# main_top.net
KiCad netlist of a schematic drawn in EAGLE
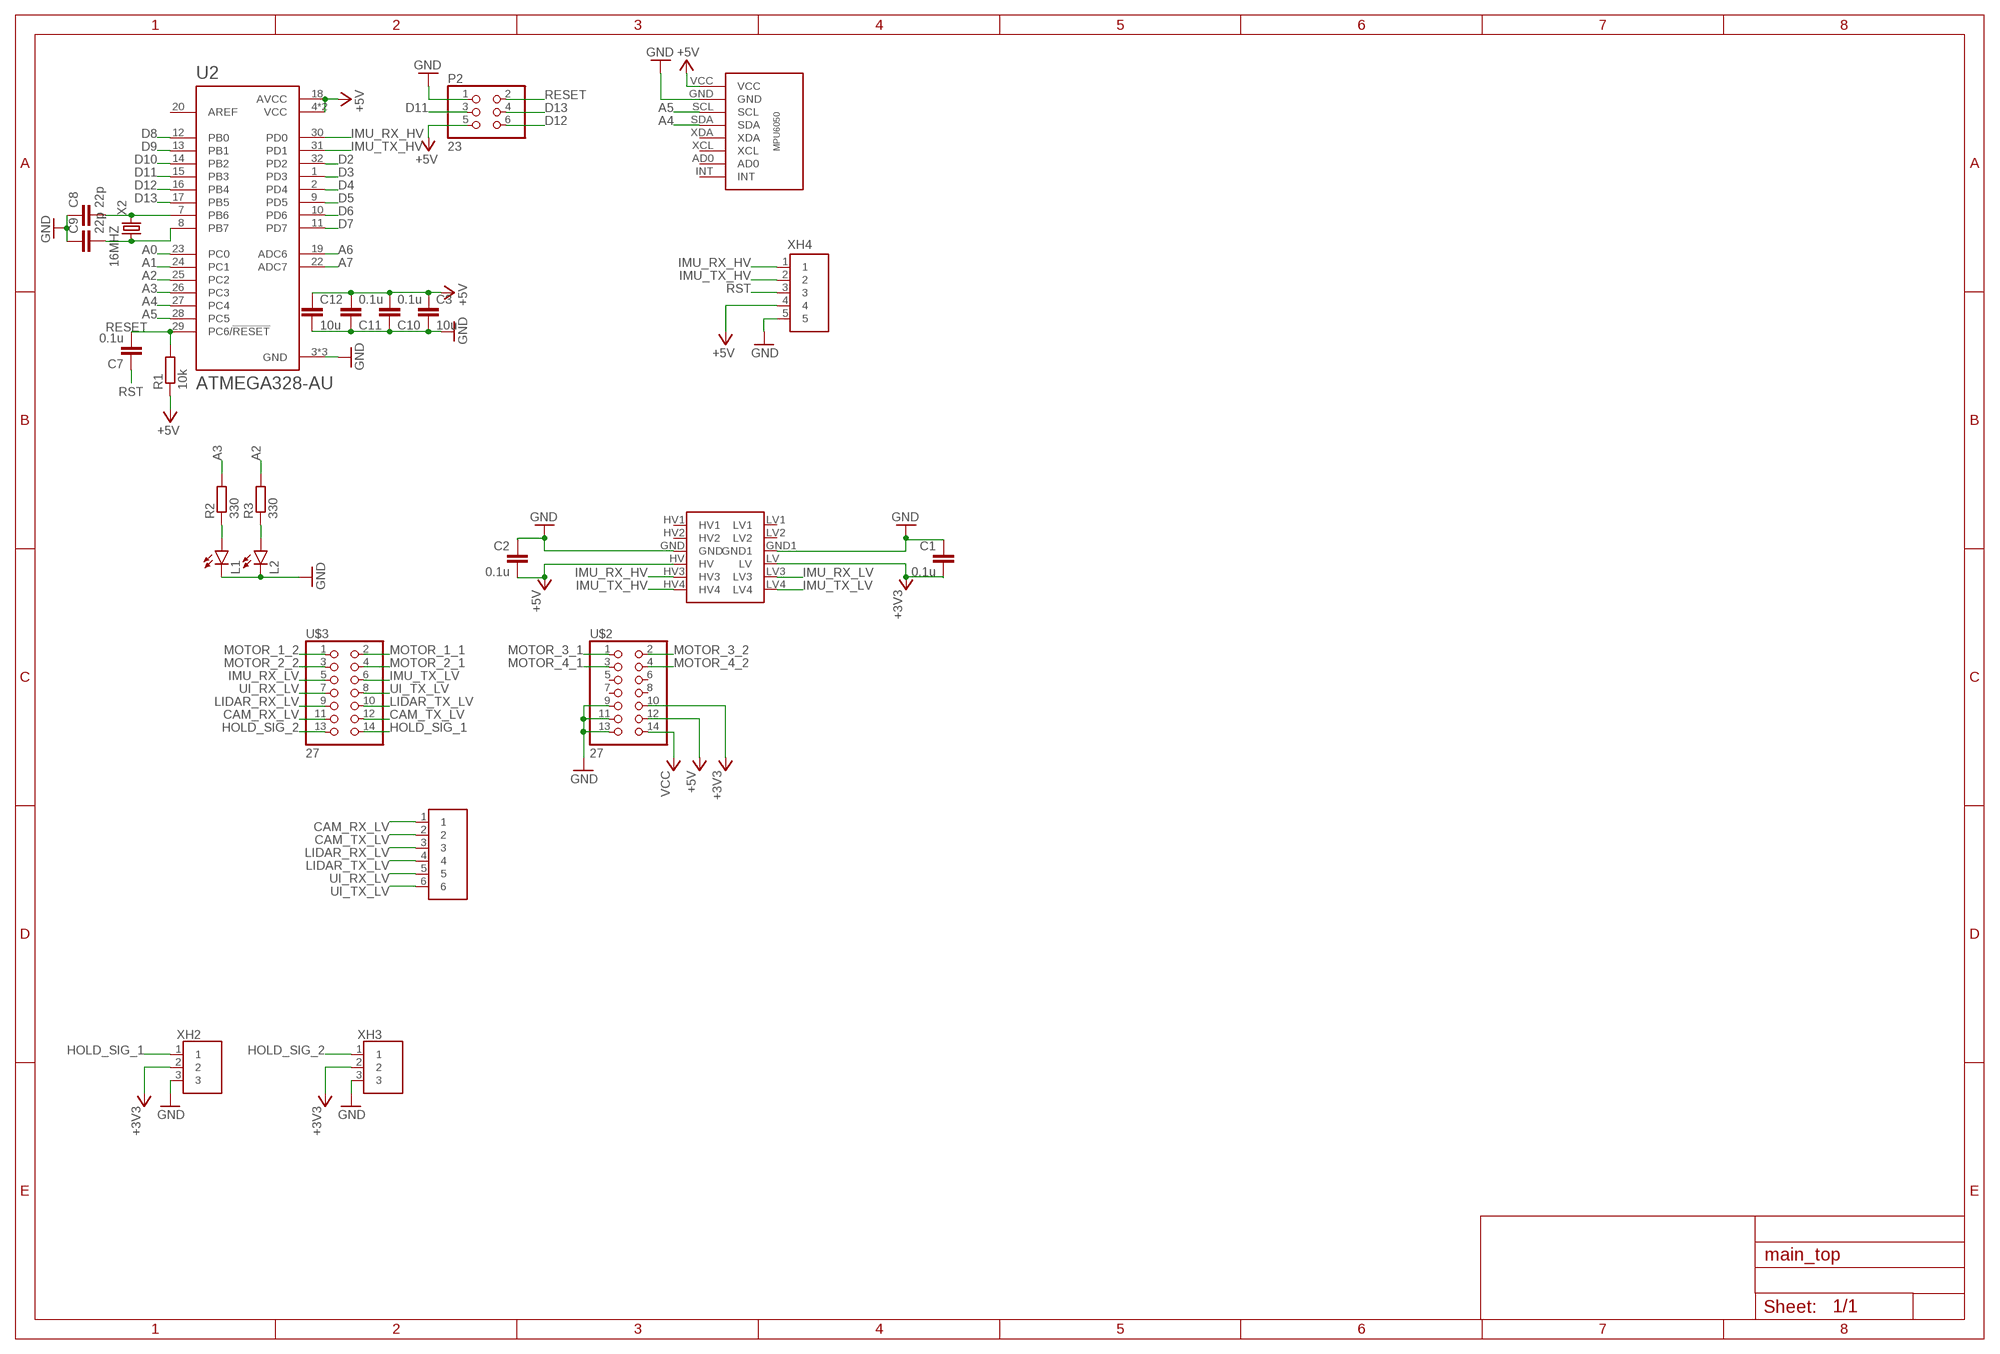
[diagram p0: schematic, sheet 1]

(export (version "E")
  (design (tool "Eeschema 10.0.6"))
  (components
    (comp (ref "C1")
      (value "0.1u")
      (footprint "eagle-import:C0603")
      (libsource (lib "eagle-import") (part "C-EUC0603"))
    )
    (comp (ref "C2")
      (value "0.1u")
      (footprint "eagle-import:C0603")
      (libsource (lib "eagle-import") (part "C-EUC0603"))
    )
    (comp (ref "C3")
      (value "10u")
      (footprint "eagle-import:C0805")
      (libsource (lib "eagle-import") (part "C-EUC0805"))
    )
    (comp (ref "C7")
      (value "0.1u")
      (footprint "eagle-import:C0603")
      (libsource (lib "eagle-import") (part "C-EUC0603"))
    )
    (comp (ref "C8")
      (value "22p")
      (footprint "eagle-import:C0603")
      (libsource (lib "eagle-import") (part "C-EUC0603"))
    )
    (comp (ref "C9")
      (value "22p")
      (footprint "eagle-import:C0603")
      (libsource (lib "eagle-import") (part "C-EUC0603"))
    )
    (comp (ref "C10")
      (value "0.1u")
      (footprint "eagle-import:C0603")
      (libsource (lib "eagle-import") (part "C-EUC0603"))
    )
    (comp (ref "C11")
      (value "0.1u")
      (footprint "eagle-import:C0603")
      (libsource (lib "eagle-import") (part "C-EUC0603"))
    )
    (comp (ref "C12")
      (value "10u")
      (footprint "eagle-import:C0805")
      (libsource (lib "eagle-import") (part "C-EUC0805"))
    )
    (comp (ref "L1")
      (value "SML-E12P8WT86")
      (footprint "eagle-import:LED_SML-LXFM0603SIC-TR")
      (libsource (lib "eagle-import") (part "SML-E12P8WT86"))
    )
    (comp (ref "L2")
      (value "SML-E12P8WT86")
      (footprint "eagle-import:LED_SML-LXFM0603SIC-TR")
      (libsource (lib "eagle-import") (part "SML-E12P8WT86"))
    )
    (comp (ref "P2") (value "23") (footprint "eagle-import:2_3") (libsource (lib "eagle-import") (part "23")))
    (comp (ref "Q1")
      (value "BSS138")
      (footprint "eagle-import:BSS138")
      (libsource (lib "eagle-import") (part "BSS138"))
    )
    (comp (ref "R1")
      (value "10k")
      (footprint "eagle-import:0204_5")
      (libsource (lib "eagle-import") (part "R-EU_0204/5"))
    )
    (comp (ref "R2")
      (value "330")
      (footprint "eagle-import:0204_5")
      (libsource (lib "eagle-import") (part "R-EU_0204/5"))
    )
    (comp (ref "R3")
      (value "330")
      (footprint "eagle-import:0204_5")
      (libsource (lib "eagle-import") (part "R-EU_0204/5"))
    )
    (comp (ref "U$1")
      (value "MPU6050")
      (footprint "eagle-import:MPU6050")
      (libsource (lib "eagle-import") (part "MPU6050"))
    )
    (comp (ref "U$2")
      (value "27")
      (footprint "eagle-import:2_7")
      (libsource (lib "eagle-import") (part "27"))
    )
    (comp (ref "U$3")
      (value "27")
      (footprint "eagle-import:2_7")
      (libsource (lib "eagle-import") (part "27"))
    )
    (comp (ref "U2")
      (value "ATMEGA328-AU")
      (footprint "eagle-import:QFP80P900X900X120-32N")
      (fields (field (name "MF") "Microchip"))
      (libsource (lib "eagle-import") (part "ATMEGA328-AU"))
    )
    (comp (ref "X2")
      (value "16MHZ")
      (footprint "eagle-import:16MHZ")
      (libsource (lib "eagle-import") (part "16MHZ"))
    )
    (comp (ref "XH1")
      (value "S6B")
      (footprint "eagle-import:S6B")
      (libsource (lib "eagle-import") (part "S6B"))
    )
    (comp (ref "XH2")
      (value "S3B")
      (footprint "eagle-import:S3B")
      (libsource (lib "eagle-import") (part "S3B"))
    )
    (comp (ref "XH3")
      (value "S3B")
      (footprint "eagle-import:S3B")
      (libsource (lib "eagle-import") (part "S3B"))
    )
    (comp (ref "XH4")
      (value "S5B")
      (footprint "eagle-import:S5B")
      (libsource (lib "eagle-import") (part "S5B"))
    )
  )
  (nets
    (net (code "1") (name "+3V3") (class "Default")
      (node (ref "C1") (pin "2") (pinfunction "2_2") (pintype "passive"))
      (node (ref "Q1") (pin "LV") (pinfunction "LV_LV") (pintype "bidirectional"))
      (node (ref "U$2") (pin "10") (pinfunction "10_10") (pintype "passive"))
      (node (ref "XH2") (pin "2") (pinfunction "2_2") (pintype "bidirectional"))
      (node (ref "XH3") (pin "2") (pinfunction "2_2") (pintype "bidirectional"))
    )
    (net (code "2") (name "+5V") (class "Default")
      (node (ref "C10") (pin "2") (pinfunction "2_2") (pintype "passive"))
      (node (ref "C11") (pin "2") (pinfunction "2_2") (pintype "passive"))
      (node (ref "C12") (pin "1") (pinfunction "1_1") (pintype "passive"))
      (node (ref "C2") (pin "2") (pinfunction "2_2") (pintype "passive"))
      (node (ref "C3") (pin "1") (pinfunction "1_1") (pintype "passive"))
      (node (ref "P2") (pin "5") (pinfunction "5_5") (pintype "passive"))
      (node (ref "Q1") (pin "HV") (pinfunction "HV_HV") (pintype "bidirectional"))
      (node (ref "R1") (pin "1") (pinfunction "1_1") (pintype "passive"))
      (node (ref "U$1") (pin "VCC") (pinfunction "VCC_VCC") (pintype "bidirectional"))
      (node (ref "U$2") (pin "12") (pinfunction "12_12") (pintype "passive"))
      (node (ref "U2") (pin "18") (pinfunction "AVCC_18") (pintype "power_in"))
      (node (ref "U2") (pin "4") (pinfunction "VCC_4") (pintype "power_in"))
      (node (ref "U2") (pin "6") (pinfunction "VCC_6") (pintype "power_in"))
      (node (ref "XH4") (pin "4") (pinfunction "4_4") (pintype "bidirectional"))
    )
    (net (code "3") (name "/A0") (class "Default")
      (node (ref "U2") (pin "23") (pinfunction "PC0_23") (pintype "bidirectional"))
    )
    (net (code "4") (name "/A1") (class "Default")
      (node (ref "U2") (pin "24") (pinfunction "PC1_24") (pintype "bidirectional"))
    )
    (net (code "5") (name "/A2") (class "Default")
      (node (ref "R3") (pin "2") (pinfunction "2_2") (pintype "passive"))
      (node (ref "U2") (pin "25") (pinfunction "PC2_25") (pintype "bidirectional"))
    )
    (net (code "6") (name "/A3") (class "Default")
      (node (ref "R2") (pin "2") (pinfunction "2_2") (pintype "passive"))
      (node (ref "U2") (pin "26") (pinfunction "PC3_26") (pintype "bidirectional"))
    )
    (net (code "7") (name "/A4") (class "Default")
      (node (ref "U$1") (pin "SDA") (pinfunction "SDA_SDA") (pintype "bidirectional"))
      (node (ref "U2") (pin "27") (pinfunction "PC4_27") (pintype "bidirectional"))
    )
    (net (code "8") (name "/A5") (class "Default")
      (node (ref "U$1") (pin "SCL") (pinfunction "SCL_SCL") (pintype "bidirectional"))
      (node (ref "U2") (pin "28") (pinfunction "PC5_28") (pintype "bidirectional"))
    )
    (net (code "9") (name "/A6") (class "Default")
      (node (ref "U2") (pin "19") (pinfunction "ADC6_19") (pintype "bidirectional"))
    )
    (net (code "10") (name "/A7") (class "Default")
      (node (ref "U2") (pin "22") (pinfunction "ADC7_22") (pintype "bidirectional"))
    )
    (net (code "11") (name "/CAM_RX_LV") (class "Default")
      (node (ref "U$3") (pin "11") (pinfunction "11_11") (pintype "passive"))
      (node (ref "XH1") (pin "1") (pinfunction "1_1") (pintype "bidirectional"))
    )
    (net (code "12") (name "/CAM_TX_LV") (class "Default")
      (node (ref "U$3") (pin "12") (pinfunction "12_12") (pintype "passive"))
      (node (ref "XH1") (pin "2") (pinfunction "2_2") (pintype "bidirectional"))
    )
    (net (code "13") (name "/D2") (class "Default")
      (node (ref "U2") (pin "32") (pinfunction "PD2_32") (pintype "bidirectional"))
    )
    (net (code "14") (name "/D3") (class "Default")
      (node (ref "U2") (pin "1") (pinfunction "PD3_1") (pintype "bidirectional"))
    )
    (net (code "15") (name "/D4") (class "Default")
      (node (ref "U2") (pin "2") (pinfunction "PD4_2") (pintype "bidirectional"))
    )
    (net (code "16") (name "/D5") (class "Default")
      (node (ref "U2") (pin "9") (pinfunction "PD5_9") (pintype "bidirectional"))
    )
    (net (code "17") (name "/D6") (class "Default")
      (node (ref "U2") (pin "10") (pinfunction "PD6_10") (pintype "bidirectional"))
    )
    (net (code "18") (name "/D7") (class "Default")
      (node (ref "U2") (pin "11") (pinfunction "PD7_11") (pintype "bidirectional"))
    )
    (net (code "19") (name "/D8") (class "Default")
      (node (ref "U2") (pin "12") (pinfunction "PB0_12") (pintype "bidirectional"))
    )
    (net (code "20") (name "/D9") (class "Default")
      (node (ref "U2") (pin "13") (pinfunction "PB1_13") (pintype "bidirectional"))
    )
    (net (code "21") (name "/D10") (class "Default")
      (node (ref "U2") (pin "14") (pinfunction "PB2_14") (pintype "bidirectional"))
    )
    (net (code "22") (name "/D11") (class "Default")
      (node (ref "P2") (pin "3") (pinfunction "3_3") (pintype "passive"))
      (node (ref "U2") (pin "15") (pinfunction "PB3_15") (pintype "bidirectional"))
    )
    (net (code "23") (name "/D12") (class "Default")
      (node (ref "P2") (pin "6") (pinfunction "6_6") (pintype "passive"))
      (node (ref "U2") (pin "16") (pinfunction "PB4_16") (pintype "bidirectional"))
    )
    (net (code "24") (name "/D13") (class "Default")
      (node (ref "P2") (pin "4") (pinfunction "4_4") (pintype "passive"))
      (node (ref "U2") (pin "17") (pinfunction "PB5_17") (pintype "bidirectional"))
    )
    (net (code "25") (name "/HOLD_SIG_1") (class "Default")
      (node (ref "U$3") (pin "14") (pinfunction "14_14") (pintype "passive"))
      (node (ref "XH2") (pin "1") (pinfunction "1_1") (pintype "bidirectional"))
    )
    (net (code "26") (name "/HOLD_SIG_2") (class "Default")
      (node (ref "U$3") (pin "13") (pinfunction "13_13") (pintype "passive"))
      (node (ref "XH3") (pin "1") (pinfunction "1_1") (pintype "bidirectional"))
    )
    (net (code "27") (name "/IMU_RX_HV") (class "Default")
      (node (ref "Q1") (pin "HV3") (pinfunction "HV3_HV3") (pintype "bidirectional"))
      (node (ref "U2") (pin "30") (pinfunction "PD0_30") (pintype "bidirectional"))
      (node (ref "XH4") (pin "1") (pinfunction "1_1") (pintype "bidirectional"))
    )
    (net (code "28") (name "/IMU_RX_LV") (class "Default")
      (node (ref "Q1") (pin "LV3") (pinfunction "LV3_LV3") (pintype "bidirectional"))
      (node (ref "U$3") (pin "5") (pinfunction "5_5") (pintype "passive"))
    )
    (net (code "29") (name "/IMU_TX_HV") (class "Default")
      (node (ref "Q1") (pin "HV4") (pinfunction "HV4_HV4") (pintype "bidirectional"))
      (node (ref "U2") (pin "31") (pinfunction "PD1_31") (pintype "bidirectional"))
      (node (ref "XH4") (pin "2") (pinfunction "2_2") (pintype "bidirectional"))
    )
    (net (code "30") (name "/IMU_TX_LV") (class "Default")
      (node (ref "Q1") (pin "LV4") (pinfunction "LV4_LV4") (pintype "bidirectional"))
      (node (ref "U$3") (pin "6") (pinfunction "6_6") (pintype "passive"))
    )
    (net (code "31") (name "/LIDAR_RX_LV") (class "Default")
      (node (ref "U$3") (pin "9") (pinfunction "9_9") (pintype "passive"))
      (node (ref "XH1") (pin "3") (pinfunction "3_3") (pintype "bidirectional"))
    )
    (net (code "32") (name "/LIDAR_TX_LV") (class "Default")
      (node (ref "U$3") (pin "10") (pinfunction "10_10") (pintype "passive"))
      (node (ref "XH1") (pin "4") (pinfunction "4_4") (pintype "bidirectional"))
    )
    (net (code "33") (name "/MOTOR_1_1") (class "Default")
      (node (ref "U$3") (pin "2") (pinfunction "2_2") (pintype "passive"))
    )
    (net (code "34") (name "/MOTOR_1_2") (class "Default")
      (node (ref "U$3") (pin "1") (pinfunction "1_1") (pintype "passive"))
    )
    (net (code "35") (name "/MOTOR_2_1") (class "Default")
      (node (ref "U$3") (pin "4") (pinfunction "4_4") (pintype "passive"))
    )
    (net (code "36") (name "/MOTOR_2_2") (class "Default")
      (node (ref "U$3") (pin "3") (pinfunction "3_3") (pintype "passive"))
    )
    (net (code "37") (name "/MOTOR_3_1") (class "Default")
      (node (ref "U$2") (pin "1") (pinfunction "1_1") (pintype "passive"))
    )
    (net (code "38") (name "/MOTOR_3_2") (class "Default")
      (node (ref "U$2") (pin "2") (pinfunction "2_2") (pintype "passive"))
    )
    (net (code "39") (name "/MOTOR_4_1") (class "Default")
      (node (ref "U$2") (pin "3") (pinfunction "3_3") (pintype "passive"))
    )
    (net (code "40") (name "/MOTOR_4_2") (class "Default")
      (node (ref "U$2") (pin "4") (pinfunction "4_4") (pintype "passive"))
    )
    (net (code "41") (name "/RESET") (class "Default")
      (node (ref "C7") (pin "2") (pinfunction "2_2") (pintype "passive"))
      (node (ref "P2") (pin "2") (pinfunction "2_2") (pintype "passive"))
      (node (ref "R1") (pin "2") (pinfunction "2_2") (pintype "passive"))
      (node (ref "U2") (pin "29") (pinfunction "PC6/~{RESET}_29") (pintype "bidirectional"))
    )
    (net (code "42") (name "/RST") (class "Default")
      (node (ref "C7") (pin "1") (pinfunction "1_1") (pintype "passive"))
      (node (ref "XH4") (pin "3") (pinfunction "3_3") (pintype "bidirectional"))
    )
    (net (code "43") (name "/UI_RX_LV") (class "Default")
      (node (ref "U$3") (pin "7") (pinfunction "7_7") (pintype "passive"))
      (node (ref "XH1") (pin "5") (pinfunction "5_5") (pintype "bidirectional"))
    )
    (net (code "44") (name "/UI_TX_LV") (class "Default")
      (node (ref "U$3") (pin "8") (pinfunction "8_8") (pintype "passive"))
      (node (ref "XH1") (pin "6") (pinfunction "6_6") (pintype "bidirectional"))
    )
    (net (code "45") (name "GND") (class "Default")
      (node (ref "C1") (pin "1") (pinfunction "1_1") (pintype "passive"))
      (node (ref "C10") (pin "1") (pinfunction "1_1") (pintype "passive"))
      (node (ref "C11") (pin "1") (pinfunction "1_1") (pintype "passive"))
      (node (ref "C12") (pin "2") (pinfunction "2_2") (pintype "passive"))
      (node (ref "C2") (pin "1") (pinfunction "1_1") (pintype "passive"))
      (node (ref "C3") (pin "2") (pinfunction "2_2") (pintype "passive"))
      (node (ref "C8") (pin "1") (pinfunction "1_1") (pintype "passive"))
      (node (ref "C9") (pin "1") (pinfunction "1_1") (pintype "passive"))
      (node (ref "L1") (pin "C") (pinfunction "C_C") (pintype "passive"))
      (node (ref "L2") (pin "C") (pinfunction "C_C") (pintype "passive"))
      (node (ref "P2") (pin "1") (pinfunction "1_1") (pintype "passive"))
      (node (ref "Q1") (pin "GND") (pinfunction "GND_GND") (pintype "bidirectional"))
      (node (ref "Q1") (pin "GND1") (pinfunction "GND1_GND1") (pintype "bidirectional"))
      (node (ref "U$1") (pin "GND") (pinfunction "GND_GND") (pintype "bidirectional"))
      (node (ref "U$2") (pin "11") (pinfunction "11_11") (pintype "passive"))
      (node (ref "U$2") (pin "13") (pinfunction "13_13") (pintype "passive"))
      (node (ref "U$2") (pin "9") (pinfunction "9_9") (pintype "passive"))
      (node (ref "U2") (pin "21") (pinfunction "GND_21") (pintype "power_in"))
      (node (ref "U2") (pin "3") (pinfunction "GND_3") (pintype "power_in"))
      (node (ref "U2") (pin "5") (pinfunction "GND_5") (pintype "power_in"))
      (node (ref "XH2") (pin "3") (pinfunction "3_3") (pintype "bidirectional"))
      (node (ref "XH3") (pin "3") (pinfunction "3_3") (pintype "bidirectional"))
      (node (ref "XH4") (pin "5") (pinfunction "5_5") (pintype "bidirectional"))
    )
    (net (code "46") (name "Net-(L1-PadA)") (class "Default")
      (node (ref "L1") (pin "A") (pinfunction "A_A") (pintype "passive"))
      (node (ref "R2") (pin "1") (pinfunction "1_1") (pintype "passive"))
    )
    (net (code "47") (name "Net-(L2-PadA)") (class "Default")
      (node (ref "L2") (pin "A") (pinfunction "A_A") (pintype "passive"))
      (node (ref "R3") (pin "1") (pinfunction "1_1") (pintype "passive"))
    )
    (net (code "48") (name "Net-(U2-PB6)") (class "Default")
      (node (ref "C8") (pin "2") (pinfunction "2_2") (pintype "passive"))
      (node (ref "U2") (pin "7") (pinfunction "PB6_7") (pintype "bidirectional"))
      (node (ref "X2") (pin "P$2") (pinfunction "2_P$2") (pintype "passive"))
    )
    (net (code "49") (name "Net-(U2-PB7)") (class "Default")
      (node (ref "C9") (pin "2") (pinfunction "2_2") (pintype "passive"))
      (node (ref "U2") (pin "8") (pinfunction "PB7_8") (pintype "bidirectional"))
      (node (ref "X2") (pin "P$1") (pinfunction "1_P$1") (pintype "passive"))
    )
    (net (code "50") (name "VCC") (class "Default")
      (node (ref "U$2") (pin "14") (pinfunction "14_14") (pintype "passive"))
    )
    (net (code "51") (name "unconnected-(Q1-PadHV1)") (class "Default")
      (node (ref "Q1") (pin "HV1") (pinfunction "HV1_HV1") (pintype "bidirectional"))
    )
    (net (code "52") (name "unconnected-(Q1-PadHV2)") (class "Default")
      (node (ref "Q1") (pin "HV2") (pinfunction "HV2_HV2") (pintype "bidirectional"))
    )
    (net (code "53") (name "unconnected-(Q1-PadLV1)") (class "Default")
      (node (ref "Q1") (pin "LV1") (pinfunction "LV1_LV1") (pintype "bidirectional"))
    )
    (net (code "54") (name "unconnected-(Q1-PadLV2)") (class "Default")
      (node (ref "Q1") (pin "LV2") (pinfunction "LV2_LV2") (pintype "bidirectional"))
    )
    (net (code "55") (name "unconnected-(U$1-PadAD0)") (class "Default")
      (node (ref "U$1") (pin "AD0") (pinfunction "AD0_AD0") (pintype "bidirectional"))
    )
    (net (code "56") (name "unconnected-(U$1-PadINT)") (class "Default")
      (node (ref "U$1") (pin "INT") (pinfunction "INT_INT") (pintype "bidirectional"))
    )
    (net (code "57") (name "unconnected-(U$1-PadXCL)") (class "Default")
      (node (ref "U$1") (pin "XCL") (pinfunction "XCL_XCL") (pintype "bidirectional"))
    )
    (net (code "58") (name "unconnected-(U$1-PadXDA)") (class "Default")
      (node (ref "U$1") (pin "XDA") (pinfunction "XDA_XDA") (pintype "bidirectional"))
    )
    (net (code "59") (name "unconnected-(U$2-Pad5)") (class "Default")
      (node (ref "U$2") (pin "5") (pinfunction "5_5") (pintype "passive"))
    )
    (net (code "60") (name "unconnected-(U$2-Pad6)") (class "Default")
      (node (ref "U$2") (pin "6") (pinfunction "6_6") (pintype "passive"))
    )
    (net (code "61") (name "unconnected-(U$2-Pad7)") (class "Default")
      (node (ref "U$2") (pin "7") (pinfunction "7_7") (pintype "passive"))
    )
    (net (code "62") (name "unconnected-(U$2-Pad8)") (class "Default")
      (node (ref "U$2") (pin "8") (pinfunction "8_8") (pintype "passive"))
    )
    (net (code "63") (name "unconnected-(U2-AREF-Pad20)") (class "Default")
      (node (ref "U2") (pin "20") (pinfunction "AREF_20") (pintype "input"))
    )
  )
)
